# MCU.net
KiCad netlist of a schematic drawn in Altium Designer
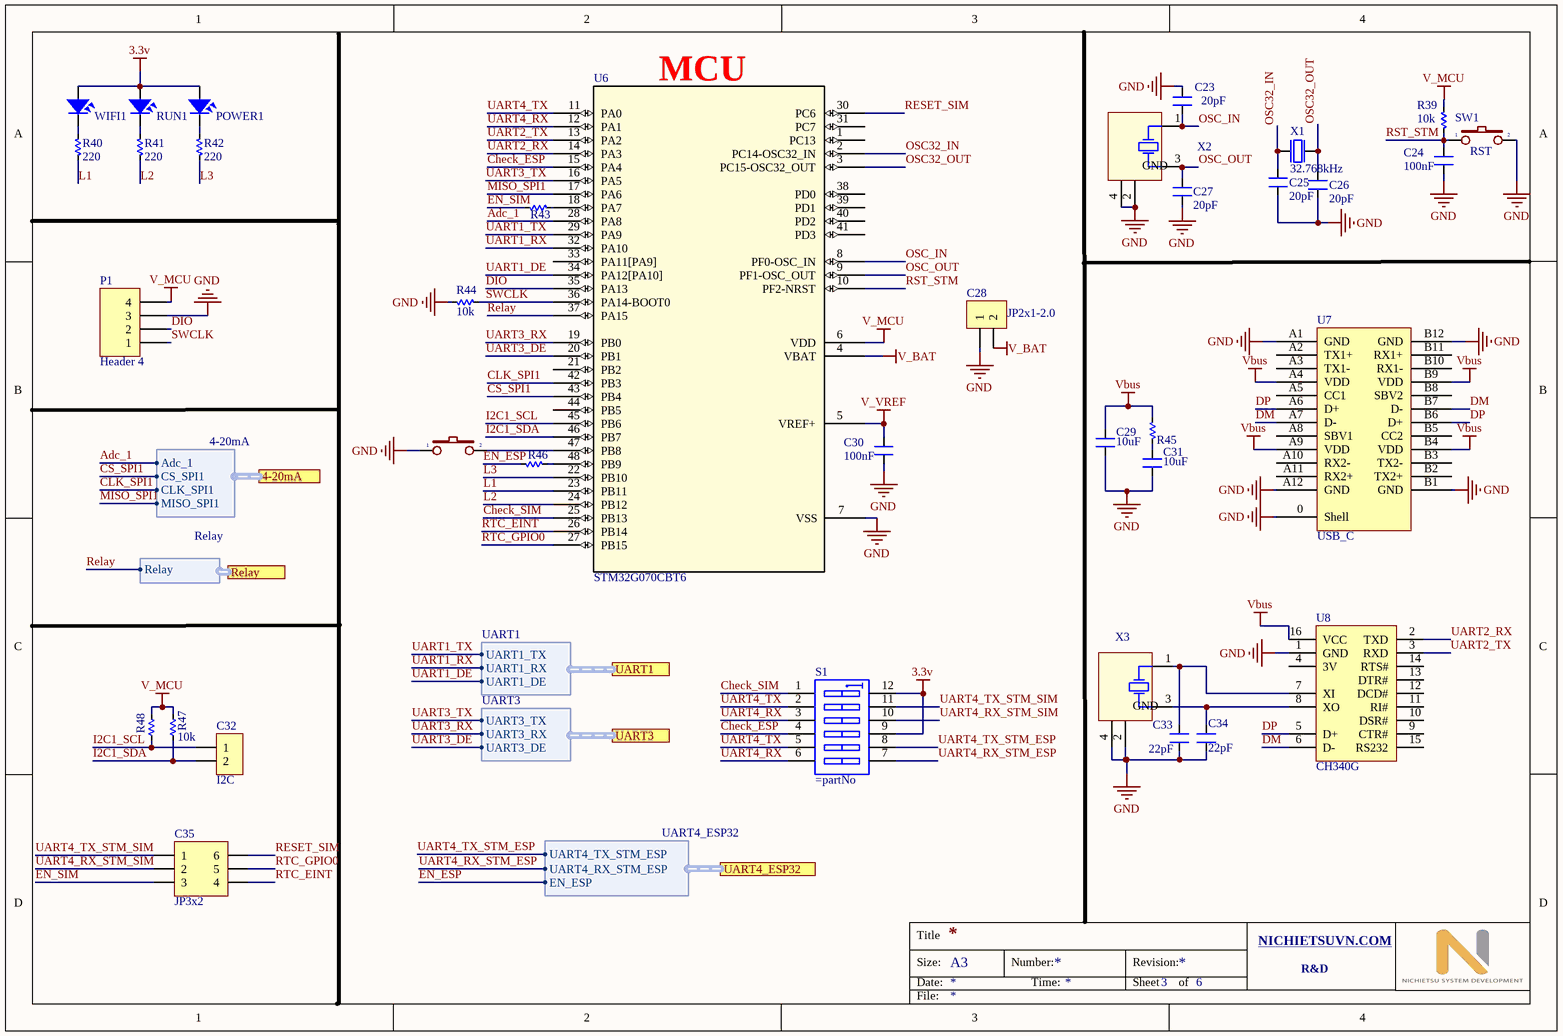
[diagram p0: MCU.SchDoc]

(export (version "E")
  (design (tool "Eeschema 10.0.6"))
  (components
    (comp (ref "C23") (value "20pF") (footprint "CN-SMD-0603") (libsource (lib "thu vien 3d") (part "CN")))
    (comp (ref "C24") (value "100nF") (footprint "CN-SMD-0603") (libsource (lib "thu vien 3d") (part "CN")))
    (comp (ref "C25") (value "20pF") (footprint "CN-SMD-0603") (libsource (lib "thu vien 3d") (part "CN")))
    (comp (ref "C26") (value "20pF") (footprint "CN-SMD-0603") (libsource (lib "thu vien 3d") (part "CN")))
    (comp (ref "C27") (value "20pF") (footprint "CN-SMD-0603") (libsource (lib "thu vien 3d") (part "CN")))
    (comp (ref "C28")
      (value "JP2x1-2.0")
      (footprint "J2-C1T")
      (description "WR-PHD 2.00 mm Socket Header")
      (fields
        (field (name "MANUFACTURER") "Würth Elektronik eiSos GmbH")
        (field (name "PARTNO") "62000211821")
        (field (name "CREATED BY") "Karrer Zheng")
      )
      (libsource (lib "thu vien 3d") (part "JP2x1-2.0"))
    )
    (comp (ref "C29") (value "10uF") (footprint "CN-SMD-0603") (libsource (lib "thu vien 3d") (part "CN")))
    (comp (ref "C30") (value "100nF") (footprint "CN-SMD-0603") (libsource (lib "thu vien 3d") (part "CN")))
    (comp (ref "C31") (value "10uF") (footprint "CN-SMD-0603") (libsource (lib "thu vien 3d") (part "CN")))
    (comp (ref "C32")
      (value "I2C")
      (footprint "J2-D1T")
      (description "WR-PHD 2.00 mm Socket Header")
      (fields
        (field (name "MANUFACTURER") "Würth Elektronik eiSos GmbH")
        (field (name "PARTNO") "62000211821")
        (field (name "CREATED BY") "Karrer Zheng")
      )
      (libsource (lib "") (part "JP2x1-2.0_1"))
    )
    (comp (ref "C33") (value "22pF") (footprint "CN-SMD-0603") (libsource (lib "thu vien 3d") (part "CN")))
    (comp (ref "C34") (value "22pF") (footprint "CN-SMD-0603") (libsource (lib "thu vien 3d") (part "CN")))
    (comp (ref "C35")
      (value "JP3x2")
      (footprint "JP3-C2T")
      (description "WR-PHD 2.54 mm Dual Socket Header")
      (fields
        (field (name "MANUFACTURER") "Würth Elektronik eiSos GmbH")
        (field (name "PARTNO") "61300621821")
        (field (name "CREATED BY") "Karrer Zheng")
      )
      (libsource (lib "thu vien 3d") (part "JP3x2"))
    )
    (comp (ref "P1")
      (value "Header 4")
      (footprint "Header 4")
      (description "Header, 4-Pin")
      (fields (field (name "PUBLISHER") "Altium Limited"))
      (libsource (lib "hphonglib") (part "Header 4"))
    )
    (comp (ref "POWER1")
      (value "LED DO SMD")
      (footprint "LED-3MM-RED")
      (description "LED Single colour Green and Red")
      (libsource (lib "thu vien 3d") (part "LED"))
    )
    (comp (ref "R39")
      (value "10k")
      (footprint "RES-SMD-0603")
      (description "Resistor")
      (fields
        (field (name "MANUFACTURER") "Generic Components")
        (field (name "PUBLISHER") "Altium Hobart Technology Centre")
      )
      (libsource (lib "thu vien 3d") (part "Res-SMD"))
    )
    (comp (ref "R40")
      (value "220")
      (footprint "RES-SMD-0603")
      (description "Resistor")
      (fields
        (field (name "MANUFACTURER") "Generic Components")
        (field (name "PUBLISHER") "Altium Hobart Technology Centre")
      )
      (libsource (lib "thu vien 3d") (part "Res-SMD"))
    )
    (comp (ref "R41")
      (value "220")
      (footprint "RES-SMD-0603")
      (description "Resistor")
      (fields
        (field (name "MANUFACTURER") "Generic Components")
        (field (name "PUBLISHER") "Altium Hobart Technology Centre")
      )
      (libsource (lib "thu vien 3d") (part "Res-SMD"))
    )
    (comp (ref "R42")
      (value "220")
      (footprint "RES-SMD-0603")
      (description "Resistor")
      (fields
        (field (name "MANUFACTURER") "Generic Components")
        (field (name "PUBLISHER") "Altium Hobart Technology Centre")
      )
      (libsource (lib "thu vien 3d") (part "Res-SMD"))
    )
    (comp (ref "R43")
      (value "10k")
      (footprint "RES-SMD-0603")
      (description "Resistor")
      (fields
        (field (name "MANUFACTURER") "Generic Components")
        (field (name "PUBLISHER") "Altium Hobart Technology Centre")
      )
      (libsource (lib "thu vien 3d") (part "Res-SMD"))
    )
    (comp (ref "R44")
      (value "10k")
      (footprint "RES-SMD-0603")
      (description "Resistor")
      (fields
        (field (name "MANUFACTURER") "Generic Components")
        (field (name "PUBLISHER") "Altium Hobart Technology Centre")
      )
      (libsource (lib "thu vien 3d") (part "Res-SMD"))
    )
    (comp (ref "R45")
      (value "2R")
      (footprint "RES-SMD-0603")
      (description "Resistor")
      (fields
        (field (name "MANUFACTURER") "Generic Components")
        (field (name "PUBLISHER") "Altium Hobart Technology Centre")
      )
      (libsource (lib "thu vien 3d") (part "Res-SMD"))
    )
    (comp (ref "R46")
      (value "1K")
      (footprint "RES-SMD-0603")
      (description "Resistor")
      (fields
        (field (name "MANUFACTURER") "Generic Components")
        (field (name "PUBLISHER") "Altium Hobart Technology Centre")
      )
      (libsource (lib "thu vien 3d") (part "Res-SMD"))
    )
    (comp (ref "R47")
      (value "10k")
      (footprint "RES-SMD-0603")
      (description "Resistor")
      (fields
        (field (name "MANUFACTURER") "Generic Components")
        (field (name "PUBLISHER") "Altium Hobart Technology Centre")
      )
      (libsource (lib "thu vien 3d") (part "Res-SMD"))
    )
    (comp (ref "R48")
      (value "10k")
      (footprint "RES-SMD-0603")
      (description "Resistor")
      (fields
        (field (name "MANUFACTURER") "Generic Components")
        (field (name "PUBLISHER") "Altium Hobart Technology Centre")
      )
      (libsource (lib "thu vien 3d") (part "Res-SMD"))
    )
    (comp (ref "RUN1")
      (value "LED VANG SMD")
      (footprint "LED-3MM-BLUE")
      (description "LED Single colour Green and Red")
      (libsource (lib "thu vien 3d") (part "LED"))
    )
    (comp (ref "S1")
      (value "~")
      (footprint "SW-DIP6")
      (description "WS-DITV 2.54 mm small compact THT flat actuator with top tape")
      (fields
        (field (name "MANUFACTURER") "Wurth Elektronik")
        (field (name "PART NO.") "418127160906")
        (field (name "CREATED BY") "Baojun Chen")
      )
      (libsource (lib "thu vien 3d") (part "SWDIP6"))
    )
    (comp (ref "SW1")
      (value "RST")
      (footprint "SW1-SMD")
      (description "Switch button 2 pin")
      (libsource (lib "thu vien 3d") (part "SW2"))
    )
    (comp (ref "SW2")
      (value "SW RESET")
      (footprint "SW1-DIP")
      (description "Switch button 2 pin")
      (libsource (lib "thu vien 3d") (part "SW2"))
    )
    (comp (ref "U6")
      (value "STM32G070CBT6")
      (footprint "STM32G070CBT6")
      (description "No Description Available")
      (fields (field (name "COPYRIGHT") "Copyright (C) 2018 Accelerated Designs. All rights reserved"))
      (libsource (lib "Nichietsuvn") (part "STM32G070CBT6"))
    )
    (comp (ref "U7") (value "USB_C") (footprint "USB-Type_C_male") (libsource (lib "Schlib2") (part "USB_C")))
    (comp (ref "U8")
      (value "CH340G")
      (footprint "SO16")
      (description "High and Low Side Driver")
      (fields (field (name "PUBLISHER") "Altium Limited"))
      (libsource (lib "thu vien 3d") (part "CH340G"))
    )
    (comp (ref "WIFI1")
      (value "LED XANH SMD")
      (footprint "LED-3MM-GREEN")
      (description "LED Single colour Green and Red")
      (libsource (lib "thu vien 3d") (part "LED"))
    )
    (comp (ref "X1")
      (value "32.768kHz")
      (footprint "XTAL_3215")
      (description "XTAL SMD 3215, 32.768kHz, Cl=9pF, Total Tol: ±50ppm")
      (fields
        (field (name "PART NUMBER") "XTAL_SMD3215_32.768kHz_9pF_General")
        (field (name "PUBLISHER") "Nordic Semiconductor")
      )
      (libsource (lib "Nichietsuvn") (part "XTAL_SMD3215"))
    )
    (comp (ref "X2")
      (value "XT4")
      (footprint "XT4-16.000MHz-4_V")
      (description "Crystal, 16 MHz, -30 to 85 degC, 3.2 x 2.5 x 0.9 mm SMD")
      (libsource (lib "thu vien 3d") (part "XT4"))
    )
    (comp (ref "X3")
      (value "XT4")
      (footprint "XT4-16.000MHz-4_V")
      (description "Crystal, 16 MHz, -30 to 85 degC, 3.2 x 2.5 x 0.9 mm SMD")
      (libsource (lib "thu vien 3d") (part "XT4"))
    )
  )
  (nets
    (net (code "5") (name "/Adc_1") (class "Default")
      (node (ref "U6") (pin "28") (pinfunction "PA8_28") (pintype "bidirectional"))
    )
    (net (code "6") (name "/CLK_SPI1") (class "Default")
      (node (ref "U6") (pin "42") (pinfunction "PB3_42") (pintype "bidirectional"))
    )
    (net (code "7") (name "/CS_SPI1") (class "Default")
      (node (ref "U6") (pin "43") (pinfunction "PB4_43") (pintype "bidirectional"))
    )
    (net (code "8") (name "/Check_ESP") (class "Default")
      (node (ref "S1") (pin "4") (pinfunction "4_4") (pintype "passive"))
      (node (ref "U6") (pin "15") (pinfunction "PA4_15") (pintype "bidirectional"))
    )
    (net (code "9") (name "/Check_SIM") (class "Default")
      (node (ref "S1") (pin "1") (pinfunction "1_1") (pintype "passive"))
      (node (ref "U6") (pin "25") (pinfunction "PB13_25") (pintype "bidirectional"))
    )
    (net (code "10") (name "/DIO") (class "Default")
      (node (ref "P1") (pin "2") (pinfunction "2_2") (pintype "passive"))
      (node (ref "U6") (pin "35") (pinfunction "PA13_35") (pintype "bidirectional"))
    )
    (net (code "11") (name "/DM") (class "Default")
      (node (ref "U7") (pin "A7") (pinfunction "D-_A7") (pintype "passive"))
      (node (ref "U7") (pin "B7") (pinfunction "D-_B7") (pintype "passive"))
      (node (ref "U8") (pin "6") (pinfunction "D-_6") (pintype "passive"))
    )
    (net (code "12") (name "/DP") (class "Default")
      (node (ref "U7") (pin "A6") (pinfunction "D+_A6") (pintype "passive"))
      (node (ref "U7") (pin "B6") (pinfunction "D+_B6") (pintype "passive"))
      (node (ref "U8") (pin "5") (pinfunction "D+_5") (pintype "passive"))
    )
    (net (code "13") (name "/EN_ESP") (class "Default")
      (node (ref "R46") (pin "2") (pinfunction "2_2") (pintype "passive"))
    )
    (net (code "14") (name "/EN_SIM") (class "Default")
      (node (ref "C35") (pin "3") (pinfunction "3_3") (pintype "passive"))
      (node (ref "R43") (pin "2") (pinfunction "2_2") (pintype "passive"))
    )
    (net (code "15") (name "/I2C1_SCL") (class "Default")
      (node (ref "C32") (pin "1") (pinfunction "1_1") (pintype "passive"))
      (node (ref "R48") (pin "1") (pinfunction "1_1") (pintype "passive"))
      (node (ref "U6") (pin "45") (pinfunction "PB6_45") (pintype "bidirectional"))
    )
    (net (code "16") (name "/I2C1_SDA") (class "Default")
      (node (ref "C32") (pin "2") (pinfunction "2_2") (pintype "passive"))
      (node (ref "R47") (pin "1") (pinfunction "1_1") (pintype "passive"))
      (node (ref "U6") (pin "46") (pinfunction "PB7_46") (pintype "bidirectional"))
    )
    (net (code "17") (name "/L1") (class "Default")
      (node (ref "R40") (pin "2") (pinfunction "2_2") (pintype "passive"))
      (node (ref "U6") (pin "23") (pinfunction "PB11_23") (pintype "bidirectional"))
    )
    (net (code "18") (name "/L2") (class "Default")
      (node (ref "R41") (pin "2") (pinfunction "2_2") (pintype "passive"))
      (node (ref "U6") (pin "24") (pinfunction "PB12_24") (pintype "bidirectional"))
    )
    (net (code "19") (name "/L3") (class "Default")
      (node (ref "R42") (pin "2") (pinfunction "2_2") (pintype "passive"))
      (node (ref "U6") (pin "22") (pinfunction "PB10_22") (pintype "bidirectional"))
    )
    (net (code "20") (name "/MISO_SPI1") (class "Default")
      (node (ref "U6") (pin "17") (pinfunction "PA6_17") (pintype "bidirectional"))
    )
    (net (code "21") (name "/OSC32_IN") (class "Default")
      (node (ref "C25") (pin "2") (pinfunction "2_2") (pintype "passive"))
      (node (ref "U6") (pin "2") (pinfunction "PC14-OSC32_IN_2") (pintype "bidirectional"))
      (node (ref "X1") (pin "2") (pinfunction "out_2") (pintype "passive"))
    )
    (net (code "22") (name "/OSC32_OUT") (class "Default")
      (node (ref "C26") (pin "2") (pinfunction "2_2") (pintype "passive"))
      (node (ref "U6") (pin "3") (pinfunction "PC15-OSC32_OUT_3") (pintype "bidirectional"))
      (node (ref "X1") (pin "1") (pinfunction "inp_1") (pintype "passive"))
    )
    (net (code "23") (name "/OSC_IN") (class "Default")
      (node (ref "C23") (pin "1") (pinfunction "1_1") (pintype "passive"))
      (node (ref "U6") (pin "8") (pinfunction "PF0-OSC_IN_8") (pintype "bidirectional"))
      (node (ref "X2") (pin "1") (pinfunction "XTAL_1") (pintype "passive"))
    )
    (net (code "24") (name "/OSC_OUT") (class "Default")
      (node (ref "C27") (pin "2") (pinfunction "2_2") (pintype "passive"))
      (node (ref "U6") (pin "9") (pinfunction "PF1-OSC_OUT_9") (pintype "bidirectional"))
      (node (ref "X2") (pin "3") (pinfunction "XTAL_3") (pintype "passive"))
    )
    (net (code "25") (name "/RESET_SIM") (class "Default")
      (node (ref "C35") (pin "6") (pinfunction "6_6") (pintype "passive"))
      (node (ref "U6") (pin "30") (pinfunction "PC6_30") (pintype "bidirectional"))
    )
    (net (code "26") (name "/RST_STM") (class "Default")
      (node (ref "C24") (pin "1") (pinfunction "1_1") (pintype "passive"))
      (node (ref "R39") (pin "2") (pinfunction "2_2") (pintype "passive"))
      (node (ref "SW1") (pin "1") (pinfunction "1_1") (pintype "passive"))
      (node (ref "U6") (pin "10") (pinfunction "PF2-NRST_10") (pintype "bidirectional"))
    )
    (net (code "27") (name "/RTC_EINT") (class "Default")
      (node (ref "C35") (pin "4") (pinfunction "4_4") (pintype "passive"))
      (node (ref "U6") (pin "26") (pinfunction "PB14_26") (pintype "bidirectional"))
    )
    (net (code "28") (name "/RTC_GPIO0") (class "Default")
      (node (ref "C35") (pin "5") (pinfunction "5_5") (pintype "passive"))
      (node (ref "U6") (pin "27") (pinfunction "PB15_27") (pintype "bidirectional"))
    )
    (net (code "29") (name "/Relay") (class "Default")
      (node (ref "U6") (pin "37") (pinfunction "PA15_37") (pintype "bidirectional"))
    )
    (net (code "30") (name "/SWCLK") (class "Default")
      (node (ref "P1") (pin "1") (pinfunction "1_1") (pintype "passive"))
      (node (ref "R44") (pin "1") (pinfunction "1_1") (pintype "passive"))
      (node (ref "U6") (pin "36") (pinfunction "PA14-BOOT0_36") (pintype "bidirectional"))
    )
    (net (code "31") (name "/UART1_DE") (class "Default")
      (node (ref "U6") (pin "34") (pinfunction "PA12[PA10]_34") (pintype "bidirectional"))
    )
    (net (code "32") (name "/UART1_RX") (class "Default")
      (node (ref "U6") (pin "32") (pinfunction "PA10_32") (pintype "bidirectional"))
    )
    (net (code "33") (name "/UART1_TX") (class "Default")
      (node (ref "U6") (pin "29") (pinfunction "PA9_29") (pintype "bidirectional"))
    )
    (net (code "34") (name "/UART2_RX") (class "Default")
      (node (ref "U6") (pin "14") (pinfunction "PA3_14") (pintype "bidirectional"))
      (node (ref "U8") (pin "2") (pinfunction "TXD_2") (pintype "passive"))
    )
    (net (code "35") (name "/UART2_TX") (class "Default")
      (node (ref "U6") (pin "13") (pinfunction "PA2_13") (pintype "bidirectional"))
      (node (ref "U8") (pin "3") (pinfunction "RXD_3") (pintype "passive"))
    )
    (net (code "36") (name "/UART3_DE") (class "Default")
      (node (ref "U6") (pin "20") (pinfunction "PB1_20") (pintype "bidirectional"))
    )
    (net (code "37") (name "/UART3_RX") (class "Default")
      (node (ref "U6") (pin "19") (pinfunction "PB0_19") (pintype "bidirectional"))
    )
    (net (code "38") (name "/UART3_TX") (class "Default")
      (node (ref "U6") (pin "16") (pinfunction "PA5_16") (pintype "bidirectional"))
    )
    (net (code "39") (name "/UART4_RX") (class "Default")
      (node (ref "S1") (pin "3") (pinfunction "3_3") (pintype "passive"))
      (node (ref "S1") (pin "6") (pinfunction "6_6") (pintype "passive"))
      (node (ref "U6") (pin "12") (pinfunction "PA1_12") (pintype "bidirectional"))
    )
    (net (code "40") (name "/UART4_RX_STM_ESP") (class "Default")
      (node (ref "S1") (pin "7") (pinfunction "7_7") (pintype "passive"))
    )
    (net (code "41") (name "/UART4_RX_STM_SIM") (class "Default")
      (node (ref "C35") (pin "2") (pinfunction "2_2") (pintype "passive"))
      (node (ref "S1") (pin "10") (pinfunction "10_10") (pintype "passive"))
    )
    (net (code "42") (name "/UART4_TX") (class "Default")
      (node (ref "S1") (pin "2") (pinfunction "2_2") (pintype "passive"))
      (node (ref "S1") (pin "5") (pinfunction "5_5") (pintype "passive"))
      (node (ref "U6") (pin "11") (pinfunction "PA0_11") (pintype "bidirectional"))
    )
    (net (code "43") (name "/UART4_TX_STM_ESP") (class "Default")
      (node (ref "S1") (pin "8") (pinfunction "8_8") (pintype "passive"))
    )
    (net (code "44") (name "/UART4_TX_STM_SIM") (class "Default")
      (node (ref "C35") (pin "1") (pinfunction "1_1") (pintype "passive"))
      (node (ref "S1") (pin "11") (pinfunction "11_11") (pintype "passive"))
    )
    (net (code "50") (name "3.3v") (class "Default")
      (node (ref "POWER1") (pin "1") (pinfunction "1_1") (pintype "passive"))
      (node (ref "RUN1") (pin "1") (pinfunction "1_1") (pintype "passive"))
      (node (ref "S1") (pin "12") (pinfunction "12_12") (pintype "passive"))
      (node (ref "S1") (pin "9") (pinfunction "9_9") (pintype "passive"))
      (node (ref "WIFI1") (pin "1") (pinfunction "1_1") (pintype "passive"))
    )
    (net (code "51") (name "GND") (class "Default")
      (node (ref "C23") (pin "2") (pinfunction "2_2") (pintype "passive"))
      (node (ref "C24") (pin "2") (pinfunction "2_2") (pintype "passive"))
      (node (ref "C25") (pin "1") (pinfunction "1_1") (pintype "passive"))
      (node (ref "C26") (pin "1") (pinfunction "1_1") (pintype "passive"))
      (node (ref "C27") (pin "1") (pinfunction "1_1") (pintype "passive"))
      (node (ref "C28") (pin "1") (pinfunction "1_1") (pintype "passive"))
      (node (ref "C29") (pin "1") (pinfunction "1_1") (pintype "passive"))
      (node (ref "C30") (pin "2") (pinfunction "2_2") (pintype "passive"))
      (node (ref "C31") (pin "1") (pinfunction "1_1") (pintype "passive"))
      (node (ref "C33") (pin "1") (pinfunction "1_1") (pintype "passive"))
      (node (ref "C34") (pin "1") (pinfunction "1_1") (pintype "passive"))
      (node (ref "P1") (pin "3") (pinfunction "3_3") (pintype "passive"))
      (node (ref "R44") (pin "2") (pinfunction "2_2") (pintype "passive"))
      (node (ref "SW1") (pin "2") (pinfunction "2_2") (pintype "passive"))
      (node (ref "SW2") (pin "1") (pinfunction "1_1") (pintype "passive"))
      (node (ref "U6") (pin "7") (pinfunction "VSS_7") (pintype "power_in"))
      (node (ref "U7") (pin "0") (pinfunction "Shell_0") (pintype "passive"))
      (node (ref "U7") (pin "A1") (pinfunction "GND_A1") (pintype "passive"))
      (node (ref "U7") (pin "A12") (pinfunction "GND_A12") (pintype "passive"))
      (node (ref "U7") (pin "B1") (pinfunction "GND_B1") (pintype "passive"))
      (node (ref "U7") (pin "B12") (pinfunction "GND_B12") (pintype "passive"))
      (node (ref "U8") (pin "1") (pinfunction "GND_1") (pintype "passive"))
      (node (ref "X2") (pin "2") (pinfunction "GND_2") (pintype "power_in"))
      (node (ref "X2") (pin "4") (pinfunction "GND_4") (pintype "power_in"))
      (node (ref "X3") (pin "2") (pinfunction "GND_2") (pintype "power_in"))
      (node (ref "X3") (pin "4") (pinfunction "GND_4") (pintype "power_in"))
    )
    (net (code "52") (name "Net-(C31-Pad2)") (class "Default")
      (node (ref "C31") (pin "2") (pinfunction "2_2") (pintype "passive"))
      (node (ref "R45") (pin "1") (pinfunction "1_1") (pintype "passive"))
    )
    (net (code "53") (name "Net-(POWER1-Pad2)") (class "Default")
      (node (ref "POWER1") (pin "2") (pinfunction "2_2") (pintype "passive"))
      (node (ref "R42") (pin "1") (pinfunction "1_1") (pintype "passive"))
    )
    (net (code "54") (name "Net-(R40-Pad1)") (class "Default")
      (node (ref "R40") (pin "1") (pinfunction "1_1") (pintype "passive"))
      (node (ref "WIFI1") (pin "2") (pinfunction "2_2") (pintype "passive"))
    )
    (net (code "55") (name "Net-(R41-Pad1)") (class "Default")
      (node (ref "R41") (pin "1") (pinfunction "1_1") (pintype "passive"))
      (node (ref "RUN1") (pin "2") (pinfunction "2_2") (pintype "passive"))
    )
    (net (code "56") (name "Net-(U6-PA7)") (class "Default")
      (node (ref "R43") (pin "1") (pinfunction "1_1") (pintype "passive"))
      (node (ref "U6") (pin "18") (pinfunction "PA7_18") (pintype "bidirectional"))
    )
    (net (code "57") (name "Net-(U6-PB8)") (class "Default")
      (node (ref "SW2") (pin "2") (pinfunction "2_2") (pintype "passive"))
      (node (ref "U6") (pin "47") (pinfunction "PB8_47") (pintype "bidirectional"))
    )
    (net (code "58") (name "Net-(U6-PB9)") (class "Default")
      (node (ref "R46") (pin "1") (pinfunction "1_1") (pintype "passive"))
      (node (ref "U6") (pin "48") (pinfunction "PB9_48") (pintype "bidirectional"))
    )
    (net (code "59") (name "Net-(U8-XI)") (class "Default")
      (node (ref "C33") (pin "2") (pinfunction "2_2") (pintype "passive"))
      (node (ref "U8") (pin "7") (pinfunction "XI_7") (pintype "passive"))
      (node (ref "X3") (pin "1") (pinfunction "XTAL_1") (pintype "passive"))
    )
    (net (code "60") (name "Net-(U8-XO)") (class "Default")
      (node (ref "C34") (pin "2") (pinfunction "2_2") (pintype "passive"))
      (node (ref "U8") (pin "8") (pinfunction "XO_8") (pintype "passive"))
      (node (ref "X3") (pin "3") (pinfunction "XTAL_3") (pintype "passive"))
    )
    (net (code "61") (name "V_BAT") (class "Default")
      (node (ref "C28") (pin "2") (pinfunction "2_2") (pintype "passive"))
      (node (ref "U6") (pin "4") (pinfunction "VBAT_4") (pintype "power_in"))
    )
    (net (code "62") (name "V_MCU") (class "Default")
      (node (ref "P1") (pin "4") (pinfunction "4_4") (pintype "passive"))
      (node (ref "R39") (pin "1") (pinfunction "1_1") (pintype "passive"))
      (node (ref "R47") (pin "2") (pinfunction "2_2") (pintype "passive"))
      (node (ref "R48") (pin "2") (pinfunction "2_2") (pintype "passive"))
      (node (ref "U6") (pin "6") (pinfunction "VDD_6") (pintype "power_in"))
    )
    (net (code "63") (name "V_VREF") (class "Default")
      (node (ref "C30") (pin "1") (pinfunction "1_1") (pintype "passive"))
      (node (ref "U6") (pin "5") (pinfunction "VREF+_5") (pintype "power_in"))
    )
    (net (code "64") (name "Vbus") (class "Default")
      (node (ref "C29") (pin "2") (pinfunction "2_2") (pintype "passive"))
      (node (ref "R45") (pin "2") (pinfunction "2_2") (pintype "passive"))
      (node (ref "U7") (pin "A4") (pinfunction "VDD_A4") (pintype "passive"))
      (node (ref "U7") (pin "A9") (pinfunction "VDD_A9") (pintype "passive"))
      (node (ref "U7") (pin "B4") (pinfunction "VDD_B4") (pintype "passive"))
      (node (ref "U7") (pin "B9") (pinfunction "VDD_B9") (pintype "passive"))
      (node (ref "U8") (pin "16") (pinfunction "VCC_16") (pintype "passive"))
    )
    (net (code "65") (name "unconnected-(U6-PA11[PA9]-Pad33)") (class "Default")
      (node (ref "U6") (pin "33") (pinfunction "PA11[PA9]_33") (pintype "bidirectional"))
    )
    (net (code "66") (name "unconnected-(U6-PB2-Pad21)") (class "Default")
      (node (ref "U6") (pin "21") (pinfunction "PB2_21") (pintype "bidirectional"))
    )
    (net (code "67") (name "unconnected-(U6-PB5-Pad44)") (class "Default")
      (node (ref "U6") (pin "44") (pinfunction "PB5_44") (pintype "bidirectional"))
    )
    (net (code "68") (name "unconnected-(U6-PC7-Pad31)") (class "Default")
      (node (ref "U6") (pin "31") (pinfunction "PC7_31") (pintype "bidirectional"))
    )
    (net (code "69") (name "unconnected-(U6-PC13-Pad1)") (class "Default")
      (node (ref "U6") (pin "1") (pinfunction "PC13_1") (pintype "bidirectional"))
    )
    (net (code "70") (name "unconnected-(U6-PD0-Pad38)") (class "Default")
      (node (ref "U6") (pin "38") (pinfunction "PD0_38") (pintype "bidirectional"))
    )
    (net (code "71") (name "unconnected-(U6-PD1-Pad39)") (class "Default")
      (node (ref "U6") (pin "39") (pinfunction "PD1_39") (pintype "bidirectional"))
    )
    (net (code "72") (name "unconnected-(U6-PD2-Pad40)") (class "Default")
      (node (ref "U6") (pin "40") (pinfunction "PD2_40") (pintype "bidirectional"))
    )
    (net (code "73") (name "unconnected-(U6-PD3-Pad41)") (class "Default")
      (node (ref "U6") (pin "41") (pinfunction "PD3_41") (pintype "bidirectional"))
    )
    (net (code "74") (name "unconnected-(U7-CC1-PadA5)") (class "Default")
      (node (ref "U7") (pin "A5") (pinfunction "CC1_A5") (pintype "passive"))
    )
    (net (code "75") (name "unconnected-(U7-CC2-PadB5)") (class "Default")
      (node (ref "U7") (pin "B5") (pinfunction "CC2_B5") (pintype "passive"))
    )
    (net (code "76") (name "unconnected-(U7-RX1+-PadB11)") (class "Default")
      (node (ref "U7") (pin "B11") (pinfunction "RX1+_B11") (pintype "passive"))
    )
    (net (code "77") (name "unconnected-(U7-RX1--PadB10)") (class "Default")
      (node (ref "U7") (pin "B10") (pinfunction "RX1-_B10") (pintype "passive"))
    )
    (net (code "78") (name "unconnected-(U7-RX2+-PadA11)") (class "Default")
      (node (ref "U7") (pin "A11") (pinfunction "RX2+_A11") (pintype "passive"))
    )
    (net (code "79") (name "unconnected-(U7-RX2--PadA10)") (class "Default")
      (node (ref "U7") (pin "A10") (pinfunction "RX2-_A10") (pintype "passive"))
    )
    (net (code "80") (name "unconnected-(U7-SBV1-PadA8)") (class "Default")
      (node (ref "U7") (pin "A8") (pinfunction "SBV1_A8") (pintype "passive"))
    )
    (net (code "81") (name "unconnected-(U7-SBV2-PadB8)") (class "Default")
      (node (ref "U7") (pin "B8") (pinfunction "SBV2_B8") (pintype "passive"))
    )
    (net (code "82") (name "unconnected-(U7-TX1+-PadA2)") (class "Default")
      (node (ref "U7") (pin "A2") (pinfunction "TX1+_A2") (pintype "passive"))
    )
    (net (code "83") (name "unconnected-(U7-TX1--PadA3)") (class "Default")
      (node (ref "U7") (pin "A3") (pinfunction "TX1-_A3") (pintype "passive"))
    )
    (net (code "84") (name "unconnected-(U7-TX2+-PadB2)") (class "Default")
      (node (ref "U7") (pin "B2") (pinfunction "TX2+_B2") (pintype "passive"))
    )
    (net (code "85") (name "unconnected-(U7-TX2--PadB3)") (class "Default")
      (node (ref "U7") (pin "B3") (pinfunction "TX2-_B3") (pintype "passive"))
    )
    (net (code "86") (name "unconnected-(U8-3V-Pad4)") (class "Default")
      (node (ref "U8") (pin "4") (pinfunction "3V_4") (pintype "passive"))
    )
    (net (code "87") (name "unconnected-(U8-CTR#-Pad9)") (class "Default")
      (node (ref "U8") (pin "9") (pinfunction "CTR#_9") (pintype "passive"))
    )
    (net (code "88") (name "unconnected-(U8-DCD#-Pad12)") (class "Default")
      (node (ref "U8") (pin "12") (pinfunction "DCD#_12") (pintype "passive"))
    )
    (net (code "89") (name "unconnected-(U8-DSR#-Pad10)") (class "Default")
      (node (ref "U8") (pin "10") (pinfunction "DSR#_10") (pintype "passive"))
    )
    (net (code "90") (name "unconnected-(U8-DTR#-Pad13)") (class "Default")
      (node (ref "U8") (pin "13") (pinfunction "DTR#_13") (pintype "passive"))
    )
    (net (code "91") (name "unconnected-(U8-RI#-Pad11)") (class "Default")
      (node (ref "U8") (pin "11") (pinfunction "RI#_11") (pintype "passive"))
    )
    (net (code "92") (name "unconnected-(U8-RS232-Pad15)") (class "Default")
      (node (ref "U8") (pin "15") (pinfunction "RS232_15") (pintype "passive"))
    )
    (net (code "93") (name "unconnected-(U8-RTS#-Pad14)") (class "Default")
      (node (ref "U8") (pin "14") (pinfunction "RTS#_14") (pintype "passive"))
    )
  )
)
